# Sequencer.net
KiCad netlist of a schematic drawn in EAGLE
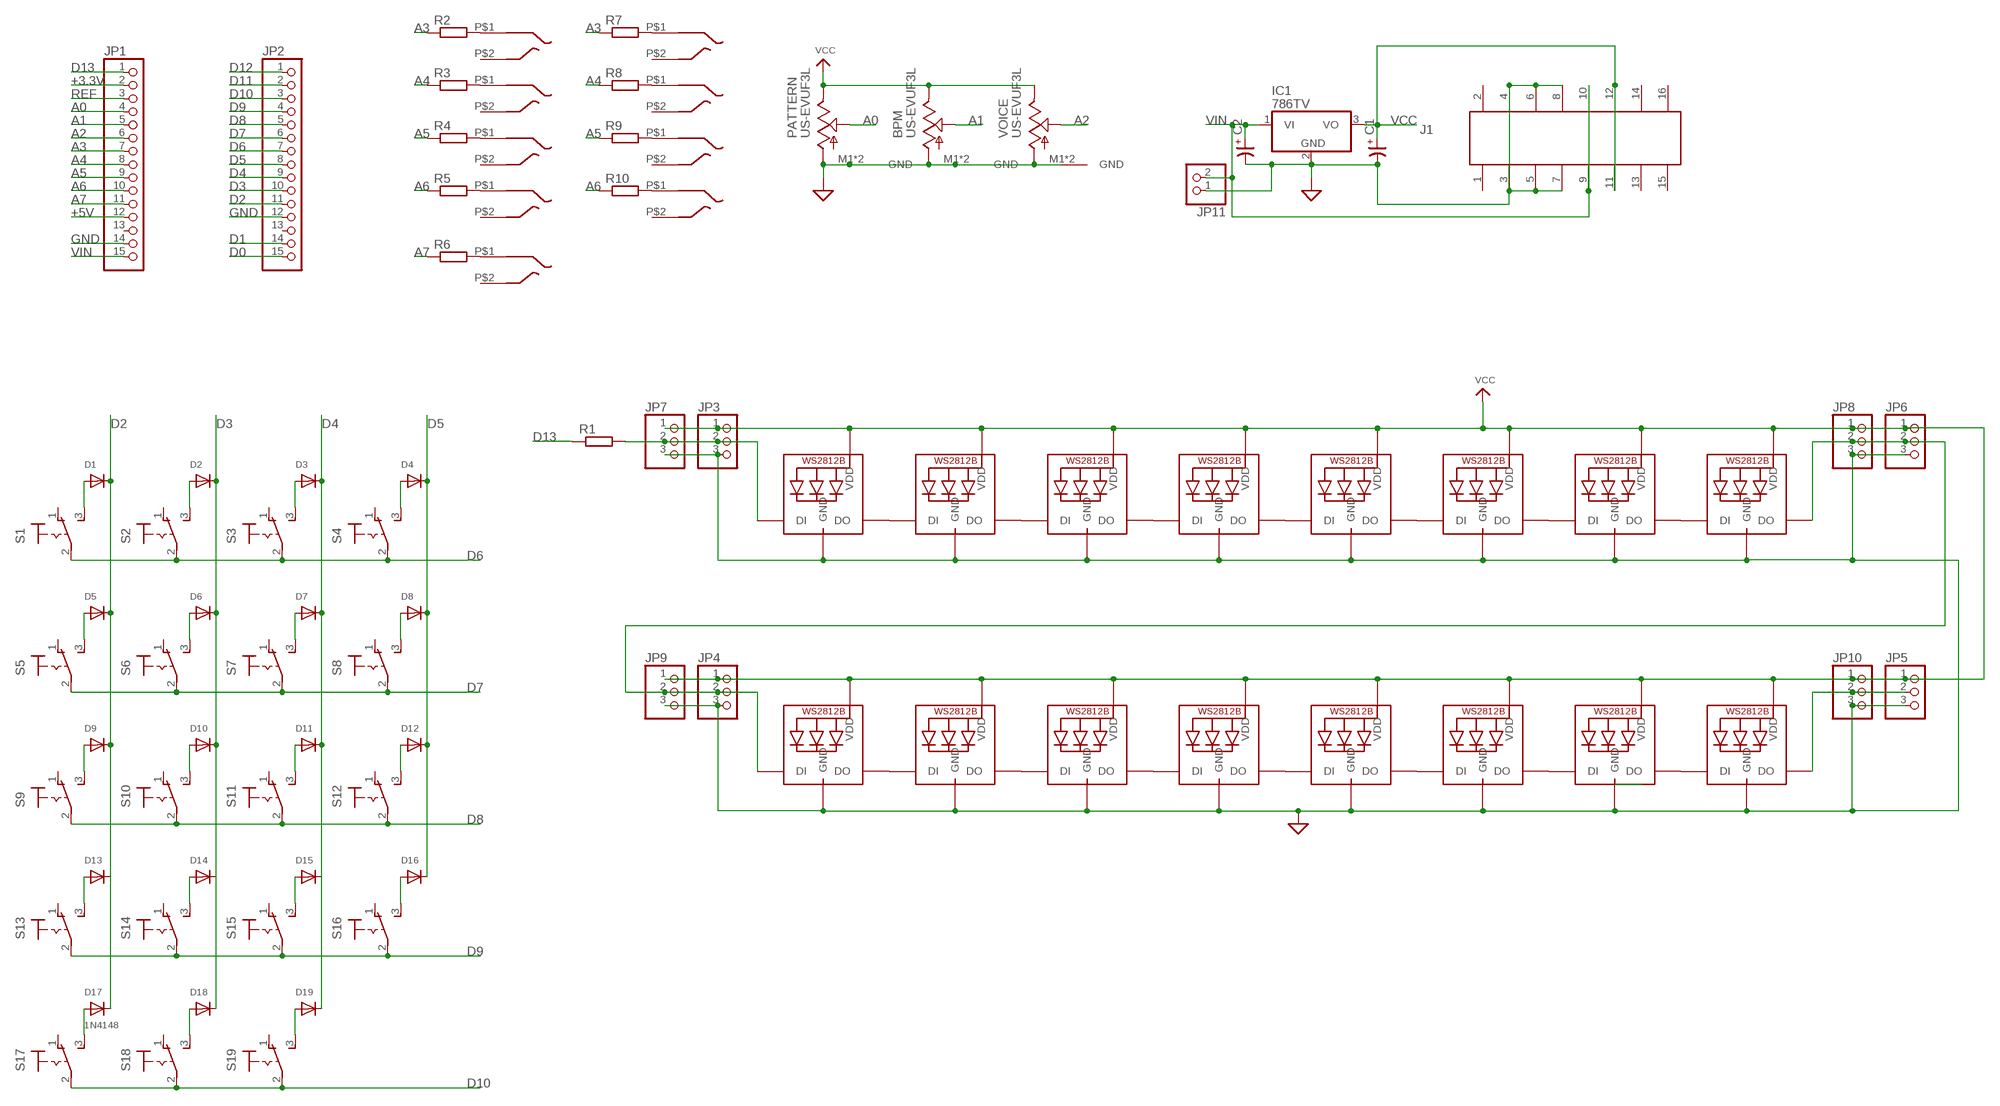
[diagram p0: schematic, sheet 1]

(export (version "E")
  (design (tool "Eeschema 10.0.6"))
  (components
    (comp (ref "BPM")
      (value "US-EVUF3L")
      (footprint "eagle-import:7.5MM")
      (libsource (lib "eagle-import") (part "US-EVULF3"))
    )
    (comp (ref "C1")
      (value "CP-E-025X065")
      (footprint "eagle-import:E-025X065")
      (libsource (lib "eagle-import") (part "CP-E-025X065"))
    )
    (comp (ref "C2")
      (value "CP-E-025X065")
      (footprint "eagle-import:E-025X065")
      (libsource (lib "eagle-import") (part "CP-E-025X065"))
    )
    (comp (ref "D1")
      (value "DIODEDO-1N4148")
      (footprint "eagle-import:DO-1N4148")
      (libsource (lib "eagle-import") (part "DIODEDO-1N4148"))
    )
    (comp (ref "D2")
      (value "DIODEDO-1N4148")
      (footprint "eagle-import:DO-1N4148")
      (libsource (lib "eagle-import") (part "DIODEDO-1N4148"))
    )
    (comp (ref "D3")
      (value "DIODEDO-1N4148")
      (footprint "eagle-import:DO-1N4148")
      (libsource (lib "eagle-import") (part "DIODEDO-1N4148"))
    )
    (comp (ref "D4")
      (value "DIODEDO-1N4148")
      (footprint "eagle-import:DO-1N4148")
      (libsource (lib "eagle-import") (part "DIODEDO-1N4148"))
    )
    (comp (ref "D5")
      (value "DIODEDO-1N4148")
      (footprint "eagle-import:DO-1N4148")
      (libsource (lib "eagle-import") (part "DIODEDO-1N4148"))
    )
    (comp (ref "D6")
      (value "DIODEDO-1N4148")
      (footprint "eagle-import:DO-1N4148")
      (libsource (lib "eagle-import") (part "DIODEDO-1N4148"))
    )
    (comp (ref "D7")
      (value "DIODEDO-1N4148")
      (footprint "eagle-import:DO-1N4148")
      (libsource (lib "eagle-import") (part "DIODEDO-1N4148"))
    )
    (comp (ref "D8")
      (value "DIODEDO-1N4148")
      (footprint "eagle-import:DO-1N4148")
      (libsource (lib "eagle-import") (part "DIODEDO-1N4148"))
    )
    (comp (ref "D9")
      (value "DIODEDO-1N4148")
      (footprint "eagle-import:DO-1N4148")
      (libsource (lib "eagle-import") (part "DIODEDO-1N4148"))
    )
    (comp (ref "D10")
      (value "DIODEDO-1N4148")
      (footprint "eagle-import:DO-1N4148")
      (libsource (lib "eagle-import") (part "DIODEDO-1N4148"))
    )
    (comp (ref "D11")
      (value "DIODEDO-1N4148")
      (footprint "eagle-import:DO-1N4148")
      (libsource (lib "eagle-import") (part "DIODEDO-1N4148"))
    )
    (comp (ref "D12")
      (value "DIODEDO-1N4148")
      (footprint "eagle-import:DO-1N4148")
      (libsource (lib "eagle-import") (part "DIODEDO-1N4148"))
    )
    (comp (ref "D13")
      (value "DIODEDO-1N4148")
      (footprint "eagle-import:DO-1N4148")
      (libsource (lib "eagle-import") (part "DIODEDO-1N4148"))
    )
    (comp (ref "D14")
      (value "DIODEDO-1N4148")
      (footprint "eagle-import:DO-1N4148")
      (libsource (lib "eagle-import") (part "DIODEDO-1N4148"))
    )
    (comp (ref "D15")
      (value "DIODEDO-1N4148")
      (footprint "eagle-import:DO-1N4148")
      (libsource (lib "eagle-import") (part "DIODEDO-1N4148"))
    )
    (comp (ref "D16")
      (value "DIODEDO-1N4148")
      (footprint "eagle-import:DO-1N4148")
      (libsource (lib "eagle-import") (part "DIODEDO-1N4148"))
    )
    (comp (ref "D17")
      (value "1N4148")
      (footprint "eagle-import:DO-1N4148")
      (libsource (lib "eagle-import") (part "DIODEDO-1N4148"))
    )
    (comp (ref "D18")
      (value "DIODEDO-1N4148")
      (footprint "eagle-import:DO-1N4148")
      (libsource (lib "eagle-import") (part "DIODEDO-1N4148"))
    )
    (comp (ref "D19")
      (value "DIODEDO-1N4148")
      (footprint "eagle-import:DO-1N4148")
      (libsource (lib "eagle-import") (part "DIODEDO-1N4148"))
    )
    (comp (ref "IC1")
      (value "786TV")
      (footprint "eagle-import:TO220V")
      (libsource (lib "eagle-import") (part "78TV6"))
    )
    (comp (ref "J1")
      (value "61201622323")
      (footprint "eagle-import:61201622323")
      (libsource (lib "eagle-import") (part "61201622323"))
    )
    (comp (ref "JP1")
      (value "PINHD-1X15")
      (footprint "eagle-import:1X15")
      (libsource (lib "eagle-import") (part "PINHD-1X15"))
    )
    (comp (ref "JP2")
      (value "PINHD-1X15")
      (footprint "eagle-import:1X15")
      (libsource (lib "eagle-import") (part "PINHD-1X15"))
    )
    (comp (ref "JP3")
      (value "PINHD-1X3CB")
      (footprint "eagle-import:1X03-CLEANBIG")
      (libsource (lib "eagle-import") (part "PINHD-1X3CB"))
    )
    (comp (ref "JP4")
      (value "PINHD-1X3CB")
      (footprint "eagle-import:1X03-CLEANBIG")
      (libsource (lib "eagle-import") (part "PINHD-1X3CB"))
    )
    (comp (ref "JP5")
      (value "PINHD-1X3CB")
      (footprint "eagle-import:1X03-CLEANBIG")
      (libsource (lib "eagle-import") (part "PINHD-1X3CB"))
    )
    (comp (ref "JP6")
      (value "PINHD-1X3CB")
      (footprint "eagle-import:1X03-CLEANBIG")
      (libsource (lib "eagle-import") (part "PINHD-1X3CB"))
    )
    (comp (ref "JP7")
      (value "PINHD-1X3CB")
      (footprint "eagle-import:1X03-CLEANBIG")
      (libsource (lib "eagle-import") (part "PINHD-1X3CB"))
    )
    (comp (ref "JP8")
      (value "PINHD-1X3CB")
      (footprint "eagle-import:1X03-CLEANBIG")
      (libsource (lib "eagle-import") (part "PINHD-1X3CB"))
    )
    (comp (ref "JP9")
      (value "PINHD-1X3CB")
      (footprint "eagle-import:1X03-CLEANBIG")
      (libsource (lib "eagle-import") (part "PINHD-1X3CB"))
    )
    (comp (ref "JP10")
      (value "PINHD-1X3CB")
      (footprint "eagle-import:1X03-CLEANBIG")
      (libsource (lib "eagle-import") (part "PINHD-1X3CB"))
    )
    (comp (ref "JP11")
      (value "PINHD-1X2")
      (footprint "eagle-import:1X02")
      (libsource (lib "eagle-import") (part "PINHD-1X2"))
    )
    (comp (ref "LED1")
      (value "WS2812B5050")
      (footprint "eagle-import:WS2812B")
      (libsource (lib "eagle-import") (part "WS2812B5050"))
    )
    (comp (ref "LED2")
      (value "WS2812B5050")
      (footprint "eagle-import:WS2812B")
      (libsource (lib "eagle-import") (part "WS2812B5050"))
    )
    (comp (ref "LED3")
      (value "WS2812B5050")
      (footprint "eagle-import:WS2812B")
      (libsource (lib "eagle-import") (part "WS2812B5050"))
    )
    (comp (ref "LED4")
      (value "WS2812B5050")
      (footprint "eagle-import:WS2812B")
      (libsource (lib "eagle-import") (part "WS2812B5050"))
    )
    (comp (ref "LED5")
      (value "WS2812B5050")
      (footprint "eagle-import:WS2812B")
      (libsource (lib "eagle-import") (part "WS2812B5050"))
    )
    (comp (ref "LED6")
      (value "WS2812B5050")
      (footprint "eagle-import:WS2812B")
      (libsource (lib "eagle-import") (part "WS2812B5050"))
    )
    (comp (ref "LED7")
      (value "WS2812B5050")
      (footprint "eagle-import:WS2812B")
      (libsource (lib "eagle-import") (part "WS2812B5050"))
    )
    (comp (ref "LED8")
      (value "WS2812B5050")
      (footprint "eagle-import:WS2812B")
      (libsource (lib "eagle-import") (part "WS2812B5050"))
    )
    (comp (ref "LED9")
      (value "WS2812B5050")
      (footprint "eagle-import:WS2812B")
      (libsource (lib "eagle-import") (part "WS2812B5050"))
    )
    (comp (ref "LED10")
      (value "WS2812B5050")
      (footprint "eagle-import:WS2812B")
      (libsource (lib "eagle-import") (part "WS2812B5050"))
    )
    (comp (ref "LED11")
      (value "WS2812B5050")
      (footprint "eagle-import:WS2812B")
      (libsource (lib "eagle-import") (part "WS2812B5050"))
    )
    (comp (ref "LED12")
      (value "WS2812B5050")
      (footprint "eagle-import:WS2812B")
      (libsource (lib "eagle-import") (part "WS2812B5050"))
    )
    (comp (ref "LED13")
      (value "WS2812B5050")
      (footprint "eagle-import:WS2812B")
      (libsource (lib "eagle-import") (part "WS2812B5050"))
    )
    (comp (ref "LED14")
      (value "WS2812B5050")
      (footprint "eagle-import:WS2812B")
      (libsource (lib "eagle-import") (part "WS2812B5050"))
    )
    (comp (ref "LED15")
      (value "WS2812B5050")
      (footprint "eagle-import:WS2812B")
      (libsource (lib "eagle-import") (part "WS2812B5050"))
    )
    (comp (ref "LED16")
      (value "WS2812B5050")
      (footprint "eagle-import:WS2812B")
      (libsource (lib "eagle-import") (part "WS2812B5050"))
    )
    (comp (ref "PATTERN")
      (value "US-EVUF3L")
      (footprint "eagle-import:7.5MM")
      (libsource (lib "eagle-import") (part "US-EVULF3"))
    )
    (comp (ref "R1")
      (value "R-EU_0207/10")
      (footprint "eagle-import:0207_10")
      (libsource (lib "eagle-import") (part "R-EU_0207/10"))
    )
    (comp (ref "R2")
      (value "R-EU_0207/10")
      (footprint "eagle-import:0207_10")
      (libsource (lib "eagle-import") (part "R-EU_0207/10"))
    )
    (comp (ref "R3")
      (value "R-EU_0207/10")
      (footprint "eagle-import:0207_10")
      (libsource (lib "eagle-import") (part "R-EU_0207/10"))
    )
    (comp (ref "R4")
      (value "R-EU_0207/10")
      (footprint "eagle-import:0207_10")
      (libsource (lib "eagle-import") (part "R-EU_0207/10"))
    )
    (comp (ref "R5")
      (value "R-EU_0207/10")
      (footprint "eagle-import:0207_10")
      (libsource (lib "eagle-import") (part "R-EU_0207/10"))
    )
    (comp (ref "R6")
      (value "R-EU_0207/10")
      (footprint "eagle-import:0207_10")
      (libsource (lib "eagle-import") (part "R-EU_0207/10"))
    )
    (comp (ref "R7")
      (value "R-EU_0207/10")
      (footprint "eagle-import:0207_10")
      (libsource (lib "eagle-import") (part "R-EU_0207/10"))
    )
    (comp (ref "R8")
      (value "R-EU_0207/10")
      (footprint "eagle-import:0207_10")
      (libsource (lib "eagle-import") (part "R-EU_0207/10"))
    )
    (comp (ref "R9")
      (value "R-EU_0207/10")
      (footprint "eagle-import:0207_10")
      (libsource (lib "eagle-import") (part "R-EU_0207/10"))
    )
    (comp (ref "R10")
      (value "R-EU_0207/10")
      (footprint "eagle-import:0207_10")
      (libsource (lib "eagle-import") (part "R-EU_0207/10"))
    )
    (comp (ref "S1")
      (value "CHINESIUM-TOGGLE-SWITCH")
      (footprint "eagle-import:CHINESIUM-TOGGLE-SWITCH")
      (libsource (lib "eagle-import") (part "CHINESIUM-TOGGLE-SWITCH"))
    )
    (comp (ref "S2")
      (value "CHINESIUM-TOGGLE-SWITCH")
      (footprint "eagle-import:CHINESIUM-TOGGLE-SWITCH")
      (libsource (lib "eagle-import") (part "CHINESIUM-TOGGLE-SWITCH"))
    )
    (comp (ref "S3")
      (value "CHINESIUM-TOGGLE-SWITCH")
      (footprint "eagle-import:CHINESIUM-TOGGLE-SWITCH")
      (libsource (lib "eagle-import") (part "CHINESIUM-TOGGLE-SWITCH"))
    )
    (comp (ref "S4")
      (value "CHINESIUM-TOGGLE-SWITCH")
      (footprint "eagle-import:CHINESIUM-TOGGLE-SWITCH")
      (libsource (lib "eagle-import") (part "CHINESIUM-TOGGLE-SWITCH"))
    )
    (comp (ref "S5")
      (value "CHINESIUM-TOGGLE-SWITCH")
      (footprint "eagle-import:CHINESIUM-TOGGLE-SWITCH")
      (libsource (lib "eagle-import") (part "CHINESIUM-TOGGLE-SWITCH"))
    )
    (comp (ref "S6")
      (value "CHINESIUM-TOGGLE-SWITCH")
      (footprint "eagle-import:CHINESIUM-TOGGLE-SWITCH")
      (libsource (lib "eagle-import") (part "CHINESIUM-TOGGLE-SWITCH"))
    )
    (comp (ref "S7")
      (value "CHINESIUM-TOGGLE-SWITCH")
      (footprint "eagle-import:CHINESIUM-TOGGLE-SWITCH")
      (libsource (lib "eagle-import") (part "CHINESIUM-TOGGLE-SWITCH"))
    )
    (comp (ref "S8")
      (value "CHINESIUM-TOGGLE-SWITCH")
      (footprint "eagle-import:CHINESIUM-TOGGLE-SWITCH")
      (libsource (lib "eagle-import") (part "CHINESIUM-TOGGLE-SWITCH"))
    )
    (comp (ref "S9")
      (value "CHINESIUM-TOGGLE-SWITCH")
      (footprint "eagle-import:CHINESIUM-TOGGLE-SWITCH")
      (libsource (lib "eagle-import") (part "CHINESIUM-TOGGLE-SWITCH"))
    )
    (comp (ref "S10")
      (value "CHINESIUM-TOGGLE-SWITCH")
      (footprint "eagle-import:CHINESIUM-TOGGLE-SWITCH")
      (libsource (lib "eagle-import") (part "CHINESIUM-TOGGLE-SWITCH"))
    )
    (comp (ref "S11")
      (value "CHINESIUM-TOGGLE-SWITCH")
      (footprint "eagle-import:CHINESIUM-TOGGLE-SWITCH")
      (libsource (lib "eagle-import") (part "CHINESIUM-TOGGLE-SWITCH"))
    )
    (comp (ref "S12")
      (value "CHINESIUM-TOGGLE-SWITCH")
      (footprint "eagle-import:CHINESIUM-TOGGLE-SWITCH")
      (libsource (lib "eagle-import") (part "CHINESIUM-TOGGLE-SWITCH"))
    )
    (comp (ref "S13")
      (value "CHINESIUM-TOGGLE-SWITCH")
      (footprint "eagle-import:CHINESIUM-TOGGLE-SWITCH")
      (libsource (lib "eagle-import") (part "CHINESIUM-TOGGLE-SWITCH"))
    )
    (comp (ref "S14")
      (value "CHINESIUM-TOGGLE-SWITCH")
      (footprint "eagle-import:CHINESIUM-TOGGLE-SWITCH")
      (libsource (lib "eagle-import") (part "CHINESIUM-TOGGLE-SWITCH"))
    )
    (comp (ref "S15")
      (value "CHINESIUM-TOGGLE-SWITCH")
      (footprint "eagle-import:CHINESIUM-TOGGLE-SWITCH")
      (libsource (lib "eagle-import") (part "CHINESIUM-TOGGLE-SWITCH"))
    )
    (comp (ref "S16")
      (value "CHINESIUM-TOGGLE-SWITCH")
      (footprint "eagle-import:CHINESIUM-TOGGLE-SWITCH")
      (libsource (lib "eagle-import") (part "CHINESIUM-TOGGLE-SWITCH"))
    )
    (comp (ref "S17")
      (value "CHINESIUM-TOGGLE-SWITCH")
      (footprint "eagle-import:CHINESIUM-TOGGLE-SWITCH")
      (libsource (lib "eagle-import") (part "CHINESIUM-TOGGLE-SWITCH"))
    )
    (comp (ref "S18")
      (value "CHINESIUM-TOGGLE-SWITCH")
      (footprint "eagle-import:CHINESIUM-TOGGLE-SWITCH")
      (libsource (lib "eagle-import") (part "CHINESIUM-TOGGLE-SWITCH"))
    )
    (comp (ref "S19")
      (value "CHINESIUM-TOGGLE-SWITCH")
      (footprint "eagle-import:CHINESIUM-TOGGLE-SWITCH")
      (libsource (lib "eagle-import") (part "CHINESIUM-TOGGLE-SWITCH"))
    )
    (comp (ref "U$1")
      (value "3.5MM-AUDIO")
      (footprint "eagle-import:3.5MM-AUDIO")
      (libsource (lib "eagle-import") (part "3.5MM-AUDIO"))
    )
    (comp (ref "U$2")
      (value "3.5MM-AUDIO")
      (footprint "eagle-import:3.5MM-AUDIO")
      (libsource (lib "eagle-import") (part "3.5MM-AUDIO"))
    )
    (comp (ref "U$3")
      (value "3.5MM-AUDIO")
      (footprint "eagle-import:3.5MM-AUDIO")
      (libsource (lib "eagle-import") (part "3.5MM-AUDIO"))
    )
    (comp (ref "U$4")
      (value "3.5MM-AUDIO")
      (footprint "eagle-import:3.5MM-AUDIO")
      (libsource (lib "eagle-import") (part "3.5MM-AUDIO"))
    )
    (comp (ref "U$5")
      (value "3.5MM-AUDIO")
      (footprint "eagle-import:3.5MM-AUDIO")
      (libsource (lib "eagle-import") (part "3.5MM-AUDIO"))
    )
    (comp (ref "U$6")
      (value "3.5MM-AUDIO")
      (footprint "eagle-import:3.5MM-AUDIO")
      (libsource (lib "eagle-import") (part "3.5MM-AUDIO"))
    )
    (comp (ref "U$7")
      (value "3.5MM-AUDIO")
      (footprint "eagle-import:3.5MM-AUDIO")
      (libsource (lib "eagle-import") (part "3.5MM-AUDIO"))
    )
    (comp (ref "U$8")
      (value "3.5MM-AUDIO")
      (footprint "eagle-import:3.5MM-AUDIO")
      (libsource (lib "eagle-import") (part "3.5MM-AUDIO"))
    )
    (comp (ref "U$9")
      (value "3.5MM-AUDIO")
      (footprint "eagle-import:3.5MM-AUDIO")
      (libsource (lib "eagle-import") (part "3.5MM-AUDIO"))
    )
    (comp (ref "VOICE")
      (value "US-EVUF3L")
      (footprint "eagle-import:7.5MM")
      (libsource (lib "eagle-import") (part "US-EVULF3"))
    )
  )
  (nets
    (net (code "1") (name "/+3.3V") (class "Default")
      (node (ref "JP1") (pin "2") (pinfunction "2_2") (pintype "passive"))
    )
    (net (code "2") (name "/+5V") (class "Default")
      (node (ref "JP1") (pin "12") (pinfunction "12_12") (pintype "passive"))
    )
    (net (code "3") (name "/A0") (class "Default")
      (node (ref "JP1") (pin "4") (pinfunction "4_4") (pintype "passive"))
      (node (ref "PATTERN") (pin "2") (pinfunction "S_2") (pintype "passive"))
    )
    (net (code "4") (name "/A1") (class "Default")
      (node (ref "BPM") (pin "2") (pinfunction "S_2") (pintype "passive"))
      (node (ref "JP1") (pin "5") (pinfunction "5_5") (pintype "passive"))
    )
    (net (code "5") (name "/A2") (class "Default")
      (node (ref "JP1") (pin "6") (pinfunction "6_6") (pintype "passive"))
      (node (ref "VOICE") (pin "2") (pinfunction "S_2") (pintype "passive"))
    )
    (net (code "6") (name "/A3") (class "Default")
      (node (ref "JP1") (pin "7") (pinfunction "7_7") (pintype "passive"))
      (node (ref "R2") (pin "1") (pinfunction "1_1") (pintype "passive"))
      (node (ref "R7") (pin "1") (pinfunction "1_1") (pintype "passive"))
    )
    (net (code "7") (name "/A4") (class "Default")
      (node (ref "JP1") (pin "8") (pinfunction "8_8") (pintype "passive"))
      (node (ref "R3") (pin "1") (pinfunction "1_1") (pintype "passive"))
      (node (ref "R8") (pin "1") (pinfunction "1_1") (pintype "passive"))
    )
    (net (code "8") (name "/A5") (class "Default")
      (node (ref "JP1") (pin "9") (pinfunction "9_9") (pintype "passive"))
      (node (ref "R4") (pin "1") (pinfunction "1_1") (pintype "passive"))
      (node (ref "R9") (pin "1") (pinfunction "1_1") (pintype "passive"))
    )
    (net (code "9") (name "/A6") (class "Default")
      (node (ref "JP1") (pin "10") (pinfunction "10_10") (pintype "passive"))
      (node (ref "R10") (pin "1") (pinfunction "1_1") (pintype "passive"))
      (node (ref "R5") (pin "1") (pinfunction "1_1") (pintype "passive"))
    )
    (net (code "10") (name "/A7") (class "Default")
      (node (ref "JP1") (pin "11") (pinfunction "11_11") (pintype "passive"))
      (node (ref "R6") (pin "1") (pinfunction "1_1") (pintype "passive"))
    )
    (net (code "11") (name "/D0") (class "Default")
      (node (ref "JP2") (pin "15") (pinfunction "15_15") (pintype "passive"))
    )
    (net (code "12") (name "/D1") (class "Default")
      (node (ref "JP2") (pin "14") (pinfunction "14_14") (pintype "passive"))
    )
    (net (code "13") (name "/D2") (class "Default")
      (node (ref "D1") (pin "C") (pinfunction "C_C") (pintype "passive"))
      (node (ref "D13") (pin "C") (pinfunction "C_C") (pintype "passive"))
      (node (ref "D17") (pin "C") (pinfunction "C_C") (pintype "passive"))
      (node (ref "D5") (pin "C") (pinfunction "C_C") (pintype "passive"))
      (node (ref "D9") (pin "C") (pinfunction "C_C") (pintype "passive"))
      (node (ref "JP2") (pin "11") (pinfunction "11_11") (pintype "passive"))
    )
    (net (code "14") (name "/D3") (class "Default")
      (node (ref "D10") (pin "C") (pinfunction "C_C") (pintype "passive"))
      (node (ref "D14") (pin "C") (pinfunction "C_C") (pintype "passive"))
      (node (ref "D18") (pin "C") (pinfunction "C_C") (pintype "passive"))
      (node (ref "D2") (pin "C") (pinfunction "C_C") (pintype "passive"))
      (node (ref "D6") (pin "C") (pinfunction "C_C") (pintype "passive"))
      (node (ref "JP2") (pin "10") (pinfunction "10_10") (pintype "passive"))
    )
    (net (code "15") (name "/D4") (class "Default")
      (node (ref "D11") (pin "C") (pinfunction "C_C") (pintype "passive"))
      (node (ref "D15") (pin "C") (pinfunction "C_C") (pintype "passive"))
      (node (ref "D19") (pin "C") (pinfunction "C_C") (pintype "passive"))
      (node (ref "D3") (pin "C") (pinfunction "C_C") (pintype "passive"))
      (node (ref "D7") (pin "C") (pinfunction "C_C") (pintype "passive"))
      (node (ref "JP2") (pin "9") (pinfunction "9_9") (pintype "passive"))
    )
    (net (code "16") (name "/D5") (class "Default")
      (node (ref "D12") (pin "C") (pinfunction "C_C") (pintype "passive"))
      (node (ref "D16") (pin "C") (pinfunction "C_C") (pintype "passive"))
      (node (ref "D4") (pin "C") (pinfunction "C_C") (pintype "passive"))
      (node (ref "D8") (pin "C") (pinfunction "C_C") (pintype "passive"))
      (node (ref "JP2") (pin "8") (pinfunction "8_8") (pintype "passive"))
    )
    (net (code "17") (name "/D6") (class "Default")
      (node (ref "JP2") (pin "7") (pinfunction "7_7") (pintype "passive"))
      (node (ref "S1") (pin "2") (pinfunction "P_2") (pintype "passive"))
      (node (ref "S2") (pin "2") (pinfunction "P_2") (pintype "passive"))
      (node (ref "S3") (pin "2") (pinfunction "P_2") (pintype "passive"))
      (node (ref "S4") (pin "2") (pinfunction "P_2") (pintype "passive"))
    )
    (net (code "18") (name "/D7") (class "Default")
      (node (ref "JP2") (pin "6") (pinfunction "6_6") (pintype "passive"))
      (node (ref "S5") (pin "2") (pinfunction "P_2") (pintype "passive"))
      (node (ref "S6") (pin "2") (pinfunction "P_2") (pintype "passive"))
      (node (ref "S7") (pin "2") (pinfunction "P_2") (pintype "passive"))
      (node (ref "S8") (pin "2") (pinfunction "P_2") (pintype "passive"))
    )
    (net (code "19") (name "/D8") (class "Default")
      (node (ref "JP2") (pin "5") (pinfunction "5_5") (pintype "passive"))
      (node (ref "S10") (pin "2") (pinfunction "P_2") (pintype "passive"))
      (node (ref "S11") (pin "2") (pinfunction "P_2") (pintype "passive"))
      (node (ref "S12") (pin "2") (pinfunction "P_2") (pintype "passive"))
      (node (ref "S9") (pin "2") (pinfunction "P_2") (pintype "passive"))
    )
    (net (code "20") (name "/D9") (class "Default")
      (node (ref "JP2") (pin "4") (pinfunction "4_4") (pintype "passive"))
      (node (ref "S13") (pin "2") (pinfunction "P_2") (pintype "passive"))
      (node (ref "S14") (pin "2") (pinfunction "P_2") (pintype "passive"))
      (node (ref "S15") (pin "2") (pinfunction "P_2") (pintype "passive"))
      (node (ref "S16") (pin "2") (pinfunction "P_2") (pintype "passive"))
    )
    (net (code "21") (name "/D10") (class "Default")
      (node (ref "JP2") (pin "3") (pinfunction "3_3") (pintype "passive"))
      (node (ref "S17") (pin "2") (pinfunction "P_2") (pintype "passive"))
      (node (ref "S18") (pin "2") (pinfunction "P_2") (pintype "passive"))
      (node (ref "S19") (pin "2") (pinfunction "P_2") (pintype "passive"))
    )
    (net (code "22") (name "/D11") (class "Default")
      (node (ref "JP2") (pin "2") (pinfunction "2_2") (pintype "passive"))
    )
    (net (code "23") (name "/D12") (class "Default")
      (node (ref "JP2") (pin "1") (pinfunction "1_1") (pintype "passive"))
    )
    (net (code "24") (name "/D13") (class "Default")
      (node (ref "JP1") (pin "1") (pinfunction "1_1") (pintype "passive"))
      (node (ref "R1") (pin "1") (pinfunction "1_1") (pintype "passive"))
    )
    (net (code "25") (name "/REF") (class "Default")
      (node (ref "JP1") (pin "3") (pinfunction "3_3") (pintype "passive"))
    )
    (net (code "26") (name "/VIN") (class "Default")
      (node (ref "C2") (pin "+") (pinfunction "+_+") (pintype "passive"))
      (node (ref "IC1") (pin "1") (pinfunction "VI_1") (pintype "input"))
      (node (ref "J1") (pin "10") (pinfunction "10_10") (pintype "passive"))
      (node (ref "J1") (pin "9") (pinfunction "9_9") (pintype "passive"))
      (node (ref "JP1") (pin "15") (pinfunction "15_15") (pintype "passive"))
      (node (ref "JP11") (pin "2") (pinfunction "2_2") (pintype "passive"))
    )
    (net (code "27") (name "Net-(LED1-DI)") (class "Default")
      (node (ref "JP3") (pin "2") (pinfunction "2_2") (pintype "passive"))
      (node (ref "JP7") (pin "2") (pinfunction "2_2") (pintype "passive"))
      (node (ref "LED1") (pin "4-DIN") (pinfunction "DI_4-DIN") (pintype "input"))
      (node (ref "R1") (pin "2") (pinfunction "2_2") (pintype "passive"))
    )
    (net (code "28") (name "Net-(LED1-DO)") (class "Default")
      (node (ref "LED1") (pin "2-DOUT") (pinfunction "DO_2-DOUT") (pintype "output"))
      (node (ref "LED2") (pin "4-DIN") (pinfunction "DI_4-DIN") (pintype "input"))
    )
    (net (code "29") (name "Net-(LED2-DO)") (class "Default")
      (node (ref "LED2") (pin "2-DOUT") (pinfunction "DO_2-DOUT") (pintype "output"))
      (node (ref "LED3") (pin "4-DIN") (pinfunction "DI_4-DIN") (pintype "input"))
    )
    (net (code "30") (name "Net-(LED3-DO)") (class "Default")
      (node (ref "LED3") (pin "2-DOUT") (pinfunction "DO_2-DOUT") (pintype "output"))
      (node (ref "LED4") (pin "4-DIN") (pinfunction "DI_4-DIN") (pintype "input"))
    )
    (net (code "31") (name "Net-(LED4-DO)") (class "Default")
      (node (ref "LED4") (pin "2-DOUT") (pinfunction "DO_2-DOUT") (pintype "output"))
      (node (ref "LED5") (pin "4-DIN") (pinfunction "DI_4-DIN") (pintype "input"))
    )
    (net (code "32") (name "Net-(LED5-DO)") (class "Default")
      (node (ref "LED5") (pin "2-DOUT") (pinfunction "DO_2-DOUT") (pintype "output"))
      (node (ref "LED6") (pin "4-DIN") (pinfunction "DI_4-DIN") (pintype "input"))
    )
    (net (code "33") (name "Net-(LED6-DO)") (class "Default")
      (node (ref "LED6") (pin "2-DOUT") (pinfunction "DO_2-DOUT") (pintype "output"))
      (node (ref "LED7") (pin "4-DIN") (pinfunction "DI_4-DIN") (pintype "input"))
    )
    (net (code "34") (name "Net-(LED7-DO)") (class "Default")
      (node (ref "LED7") (pin "2-DOUT") (pinfunction "DO_2-DOUT") (pintype "output"))
      (node (ref "LED8") (pin "4-DIN") (pinfunction "DI_4-DIN") (pintype "input"))
    )
    (net (code "35") (name "Net-(LED8-DO)") (class "Default")
      (node (ref "JP4") (pin "2") (pinfunction "2_2") (pintype "passive"))
      (node (ref "JP6") (pin "2") (pinfunction "2_2") (pintype "passive"))
      (node (ref "JP8") (pin "2") (pinfunction "2_2") (pintype "passive"))
      (node (ref "JP9") (pin "2") (pinfunction "2_2") (pintype "passive"))
      (node (ref "LED8") (pin "2-DOUT") (pinfunction "DO_2-DOUT") (pintype "output"))
      (node (ref "LED9") (pin "4-DIN") (pinfunction "DI_4-DIN") (pintype "input"))
    )
    (net (code "36") (name "Net-(LED10-DI)") (class "Default")
      (node (ref "LED10") (pin "4-DIN") (pinfunction "DI_4-DIN") (pintype "input"))
      (node (ref "LED9") (pin "2-DOUT") (pinfunction "DO_2-DOUT") (pintype "output"))
    )
    (net (code "37") (name "Net-(LED10-DO)") (class "Default")
      (node (ref "LED10") (pin "2-DOUT") (pinfunction "DO_2-DOUT") (pintype "output"))
      (node (ref "LED11") (pin "4-DIN") (pinfunction "DI_4-DIN") (pintype "input"))
    )
    (net (code "38") (name "Net-(LED11-DO)") (class "Default")
      (node (ref "LED11") (pin "2-DOUT") (pinfunction "DO_2-DOUT") (pintype "output"))
      (node (ref "LED12") (pin "4-DIN") (pinfunction "DI_4-DIN") (pintype "input"))
    )
    (net (code "39") (name "Net-(LED12-DO)") (class "Default")
      (node (ref "LED12") (pin "2-DOUT") (pinfunction "DO_2-DOUT") (pintype "output"))
      (node (ref "LED13") (pin "4-DIN") (pinfunction "DI_4-DIN") (pintype "input"))
    )
    (net (code "40") (name "Net-(LED13-DO)") (class "Default")
      (node (ref "LED13") (pin "2-DOUT") (pinfunction "DO_2-DOUT") (pintype "output"))
      (node (ref "LED14") (pin "4-DIN") (pinfunction "DI_4-DIN") (pintype "input"))
    )
    (net (code "41") (name "Net-(LED14-DO)") (class "Default")
      (node (ref "LED14") (pin "2-DOUT") (pinfunction "DO_2-DOUT") (pintype "output"))
      (node (ref "LED15") (pin "4-DIN") (pinfunction "DI_4-DIN") (pintype "input"))
    )
    (net (code "42") (name "Net-(LED15-DO)") (class "Default")
      (node (ref "LED15") (pin "2-DOUT") (pinfunction "DO_2-DOUT") (pintype "output"))
      (node (ref "LED16") (pin "4-DIN") (pinfunction "DI_4-DIN") (pintype "input"))
    )
    (net (code "43") (name "Net-(LED16-DO)") (class "Default")
      (node (ref "JP10") (pin "2") (pinfunction "2_2") (pintype "passive"))
      (node (ref "JP5") (pin "2") (pinfunction "2_2") (pintype "passive"))
      (node (ref "LED16") (pin "2-DOUT") (pinfunction "DO_2-DOUT") (pintype "output"))
    )
    (net (code "44") (name "Net-(S1-S)") (class "Default")
      (node (ref "D1") (pin "A") (pinfunction "A_A") (pintype "passive"))
      (node (ref "S1") (pin "3") (pinfunction "S_3") (pintype "passive"))
    )
    (net (code "45") (name "Net-(S2-S)") (class "Default")
      (node (ref "D2") (pin "A") (pinfunction "A_A") (pintype "passive"))
      (node (ref "S2") (pin "3") (pinfunction "S_3") (pintype "passive"))
    )
    (net (code "46") (name "Net-(S3-S)") (class "Default")
      (node (ref "D3") (pin "A") (pinfunction "A_A") (pintype "passive"))
      (node (ref "S3") (pin "3") (pinfunction "S_3") (pintype "passive"))
    )
    (net (code "47") (name "Net-(S4-S)") (class "Default")
      (node (ref "D4") (pin "A") (pinfunction "A_A") (pintype "passive"))
      (node (ref "S4") (pin "3") (pinfunction "S_3") (pintype "passive"))
    )
    (net (code "48") (name "Net-(S5-S)") (class "Default")
      (node (ref "D5") (pin "A") (pinfunction "A_A") (pintype "passive"))
      (node (ref "S5") (pin "3") (pinfunction "S_3") (pintype "passive"))
    )
    (net (code "49") (name "Net-(S6-S)") (class "Default")
      (node (ref "D6") (pin "A") (pinfunction "A_A") (pintype "passive"))
      (node (ref "S6") (pin "3") (pinfunction "S_3") (pintype "passive"))
    )
    (net (code "50") (name "Net-(S7-S)") (class "Default")
      (node (ref "D7") (pin "A") (pinfunction "A_A") (pintype "passive"))
      (node (ref "S7") (pin "3") (pinfunction "S_3") (pintype "passive"))
    )
    (net (code "51") (name "Net-(S8-S)") (class "Default")
      (node (ref "D8") (pin "A") (pinfunction "A_A") (pintype "passive"))
      (node (ref "S8") (pin "3") (pinfunction "S_3") (pintype "passive"))
    )
    (net (code "52") (name "Net-(S9-S)") (class "Default")
      (node (ref "D9") (pin "A") (pinfunction "A_A") (pintype "passive"))
      (node (ref "S9") (pin "3") (pinfunction "S_3") (pintype "passive"))
    )
    (net (code "53") (name "Net-(S10-S)") (class "Default")
      (node (ref "D10") (pin "A") (pinfunction "A_A") (pintype "passive"))
      (node (ref "S10") (pin "3") (pinfunction "S_3") (pintype "passive"))
    )
    (net (code "54") (name "Net-(S11-S)") (class "Default")
      (node (ref "D11") (pin "A") (pinfunction "A_A") (pintype "passive"))
      (node (ref "S11") (pin "3") (pinfunction "S_3") (pintype "passive"))
    )
    (net (code "55") (name "Net-(S12-S)") (class "Default")
      (node (ref "D12") (pin "A") (pinfunction "A_A") (pintype "passive"))
      (node (ref "S12") (pin "3") (pinfunction "S_3") (pintype "passive"))
    )
    (net (code "56") (name "Net-(S13-S)") (class "Default")
      (node (ref "D13") (pin "A") (pinfunction "A_A") (pintype "passive"))
      (node (ref "S13") (pin "3") (pinfunction "S_3") (pintype "passive"))
    )
    (net (code "57") (name "Net-(S14-S)") (class "Default")
      (node (ref "D14") (pin "A") (pinfunction "A_A") (pintype "passive"))
      (node (ref "S14") (pin "3") (pinfunction "S_3") (pintype "passive"))
    )
    (net (code "58") (name "Net-(S15-S)") (class "Default")
      (node (ref "D15") (pin "A") (pinfunction "A_A") (pintype "passive"))
      (node (ref "S15") (pin "3") (pinfunction "S_3") (pintype "passive"))
    )
    (net (code "59") (name "Net-(S16-S)") (class "Default")
      (node (ref "D16") (pin "A") (pinfunction "A_A") (pintype "passive"))
      (node (ref "S16") (pin "3") (pinfunction "S_3") (pintype "passive"))
    )
    (net (code "60") (name "Net-(S17-S)") (class "Default")
      (node (ref "D17") (pin "A") (pinfunction "A_A") (pintype "passive"))
      (node (ref "S17") (pin "3") (pinfunction "S_3") (pintype "passive"))
    )
    (net (code "61") (name "Net-(S18-S)") (class "Default")
      (node (ref "D18") (pin "A") (pinfunction "A_A") (pintype "passive"))
      (node (ref "S18") (pin "3") (pinfunction "S_3") (pintype "passive"))
    )
    (net (code "62") (name "Net-(S19-S)") (class "Default")
      (node (ref "D19") (pin "A") (pinfunction "A_A") (pintype "passive"))
      (node (ref "S19") (pin "3") (pinfunction "S_3") (pintype "passive"))
    )
    (net (code "63") (name "Net-(U$1-1)") (class "Default")
      (node (ref "R2") (pin "2") (pinfunction "2_2") (pintype "passive"))
      (node (ref "U$1") (pin "P$1") (pinfunction "1_P$1") (pintype "bidirectional"))
    )
    (net (code "64") (name "Net-(U$2-1)") (class "Default")
      (node (ref "R3") (pin "2") (pinfunction "2_2") (pintype "passive"))
      (node (ref "U$2") (pin "P$1") (pinfunction "1_P$1") (pintype "bidirectional"))
    )
    (net (code "65") (name "Net-(U$3-1)") (class "Default")
      (node (ref "R4") (pin "2") (pinfunction "2_2") (pintype "passive"))
      (node (ref "U$3") (pin "P$1") (pinfunction "1_P$1") (pintype "bidirectional"))
    )
    (net (code "66") (name "Net-(U$4-1)") (class "Default")
      (node (ref "R5") (pin "2") (pinfunction "2_2") (pintype "passive"))
      (node (ref "U$4") (pin "P$1") (pinfunction "1_P$1") (pintype "bidirectional"))
    )
    (net (code "67") (name "Net-(U$5-1)") (class "Default")
      (node (ref "R6") (pin "2") (pinfunction "2_2") (pintype "passive"))
      (node (ref "U$5") (pin "P$1") (pinfunction "1_P$1") (pintype "bidirectional"))
    )
    (net (code "68") (name "Net-(U$6-1)") (class "Default")
      (node (ref "R7") (pin "2") (pinfunction "2_2") (pintype "passive"))
      (node (ref "U$6") (pin "P$1") (pinfunction "1_P$1") (pintype "bidirectional"))
    )
    (net (code "69") (name "Net-(U$7-1)") (class "Default")
      (node (ref "R8") (pin "2") (pinfunction "2_2") (pintype "passive"))
      (node (ref "U$7") (pin "P$1") (pinfunction "1_P$1") (pintype "bidirectional"))
    )
    (net (code "70") (name "Net-(U$8-1)") (class "Default")
      (node (ref "R9") (pin "2") (pinfunction "2_2") (pintype "passive"))
      (node (ref "U$8") (pin "P$1") (pinfunction "1_P$1") (pintype "bidirectional"))
    )
    (net (code "71") (name "Net-(U$9-1)") (class "Default")
      (node (ref "R10") (pin "2") (pinfunction "2_2") (pintype "passive"))
      (node (ref "U$9") (pin "P$1") (pinfunction "1_P$1") (pintype "bidirectional"))
    )
    (net (code "72") (name "SUP") (class "Default")
      (node (ref "BPM") (pin "1") (pinfunction "A_1") (pintype "passive"))
      (node (ref "BPM") (pin "M1") (pinfunction "GND_M1") (pintype "bidirectional"))
      (node (ref "BPM") (pin "M2") (pinfunction "GND_M2") (pintype "bidirectional"))
      (node (ref "C1") (pin "-") (pinfunction "-_-") (pintype "passive"))
      (node (ref "C2") (pin "-") (pinfunction "-_-") (pintype "passive"))
      (node (ref "IC1") (pin "2") (pinfunction "GND_2") (pintype "passive"))
      (node (ref "J1") (pin "3") (pinfunction "3_3") (pintype "passive"))
      (node (ref "J1") (pin "4") (pinfunction "4_4") (pintype "passive"))
      (node (ref "J1") (pin "5") (pinfunction "5_5") (pintype "passive"))
      (node (ref "J1") (pin "6") (pinfunction "6_6") (pintype "passive"))
      (node (ref "J1") (pin "7") (pinfunction "7_7") (pintype "passive"))
      (node (ref "J1") (pin "8") (pinfunction "8_8") (pintype "passive"))
      (node (ref "JP1") (pin "14") (pinfunction "14_14") (pintype "passive"))
      (node (ref "JP10") (pin "3") (pinfunction "3_3") (pintype "passive"))
      (node (ref "JP11") (pin "1") (pinfunction "1_1") (pintype "passive"))
      (node (ref "JP2") (pin "12") (pinfunction "12_12") (pintype "passive"))
      (node (ref "JP3") (pin "3") (pinfunction "3_3") (pintype "passive"))
      (node (ref "JP4") (pin "3") (pinfunction "3_3") (pintype "passive"))
      (node (ref "JP5") (pin "3") (pinfunction "3_3") (pintype "passive"))
      (node (ref "JP6") (pin "3") (pinfunction "3_3") (pintype "passive"))
      (node (ref "JP7") (pin "3") (pinfunction "3_3") (pintype "passive"))
      (node (ref "JP8") (pin "3") (pinfunction "3_3") (pintype "passive"))
      (node (ref "JP9") (pin "3") (pinfunction "3_3") (pintype "passive"))
      (node (ref "LED1") (pin "3-GND") (pinfunction "GND_3-GND") (pintype "power_in"))
      (node (ref "LED10") (pin "3-GND") (pinfunction "GND_3-GND") (pintype "power_in"))
      (node (ref "LED11") (pin "3-GND") (pinfunction "GND_3-GND") (pintype "power_in"))
      (node (ref "LED12") (pin "3-GND") (pinfunction "GND_3-GND") (pintype "power_in"))
      (node (ref "LED13") (pin "3-GND") (pinfunction "GND_3-GND") (pintype "power_in"))
      (node (ref "LED14") (pin "3-GND") (pinfunction "GND_3-GND") (pintype "power_in"))
      (node (ref "LED15") (pin "3-GND") (pinfunction "GND_3-GND") (pintype "power_in"))
      (node (ref "LED16") (pin "3-GND") (pinfunction "GND_3-GND") (pintype "power_in"))
      (node (ref "LED2") (pin "3-GND") (pinfunction "GND_3-GND") (pintype "power_in"))
      (node (ref "LED3") (pin "3-GND") (pinfunction "GND_3-GND") (pintype "power_in"))
      (node (ref "LED4") (pin "3-GND") (pinfunction "GND_3-GND") (pintype "power_in"))
      (node (ref "LED5") (pin "3-GND") (pinfunction "GND_3-GND") (pintype "power_in"))
      (node (ref "LED6") (pin "3-GND") (pinfunction "GND_3-GND") (pintype "power_in"))
      (node (ref "LED7") (pin "3-GND") (pinfunction "GND_3-GND") (pintype "power_in"))
      (node (ref "LED8") (pin "3-GND") (pinfunction "GND_3-GND") (pintype "power_in"))
      (node (ref "LED9") (pin "3-GND") (pinfunction "GND_3-GND") (pintype "power_in"))
      (node (ref "PATTERN") (pin "1") (pinfunction "A_1") (pintype "passive"))
      (node (ref "PATTERN") (pin "M1") (pinfunction "GND_M1") (pintype "bidirectional"))
      (node (ref "PATTERN") (pin "M2") (pinfunction "GND_M2") (pintype "bidirectional"))
      (node (ref "VOICE") (pin "1") (pinfunction "A_1") (pintype "passive"))
      (node (ref "VOICE") (pin "M1") (pinfunction "GND_M1") (pintype "bidirectional"))
      (node (ref "VOICE") (pin "M2") (pinfunction "GND_M2") (pintype "bidirectional"))
    )
    (net (code "73") (name "VCC") (class "Default")
      (node (ref "BPM") (pin "3") (pinfunction "E_3") (pintype "passive"))
      (node (ref "C1") (pin "+") (pinfunction "+_+") (pintype "passive"))
      (node (ref "IC1") (pin "3") (pinfunction "VO_3") (pintype "passive"))
      (node (ref "J1") (pin "11") (pinfunction "11_11") (pintype "passive"))
      (node (ref "J1") (pin "12") (pinfunction "12_12") (pintype "passive"))
      (node (ref "JP10") (pin "1") (pinfunction "1_1") (pintype "passive"))
      (node (ref "JP3") (pin "1") (pinfunction "1_1") (pintype "passive"))
      (node (ref "JP4") (pin "1") (pinfunction "1_1") (pintype "passive"))
      (node (ref "JP5") (pin "1") (pinfunction "1_1") (pintype "passive"))
      (node (ref "JP6") (pin "1") (pinfunction "1_1") (pintype "passive"))
      (node (ref "JP7") (pin "1") (pinfunction "1_1") (pintype "passive"))
      (node (ref "JP8") (pin "1") (pinfunction "1_1") (pintype "passive"))
      (node (ref "JP9") (pin "1") (pinfunction "1_1") (pintype "passive"))
      (node (ref "LED1") (pin "1-VDD") (pinfunction "VDD_1-VDD") (pintype "power_in"))
      (node (ref "LED10") (pin "1-VDD") (pinfunction "VDD_1-VDD") (pintype "power_in"))
      (node (ref "LED11") (pin "1-VDD") (pinfunction "VDD_1-VDD") (pintype "power_in"))
      (node (ref "LED12") (pin "1-VDD") (pinfunction "VDD_1-VDD") (pintype "power_in"))
      (node (ref "LED13") (pin "1-VDD") (pinfunction "VDD_1-VDD") (pintype "power_in"))
      (node (ref "LED14") (pin "1-VDD") (pinfunction "VDD_1-VDD") (pintype "power_in"))
      (node (ref "LED15") (pin "1-VDD") (pinfunction "VDD_1-VDD") (pintype "power_in"))
      (node (ref "LED16") (pin "1-VDD") (pinfunction "VDD_1-VDD") (pintype "power_in"))
      (node (ref "LED2") (pin "1-VDD") (pinfunction "VDD_1-VDD") (pintype "power_in"))
      (node (ref "LED3") (pin "1-VDD") (pinfunction "VDD_1-VDD") (pintype "power_in"))
      (node (ref "LED4") (pin "1-VDD") (pinfunction "VDD_1-VDD") (pintype "power_in"))
      (node (ref "LED5") (pin "1-VDD") (pinfunction "VDD_1-VDD") (pintype "power_in"))
      (node (ref "LED6") (pin "1-VDD") (pinfunction "VDD_1-VDD") (pintype "power_in"))
      (node (ref "LED7") (pin "1-VDD") (pinfunction "VDD_1-VDD") (pintype "power_in"))
      (node (ref "LED8") (pin "1-VDD") (pinfunction "VDD_1-VDD") (pintype "power_in"))
      (node (ref "LED9") (pin "1-VDD") (pinfunction "VDD_1-VDD") (pintype "power_in"))
      (node (ref "PATTERN") (pin "3") (pinfunction "E_3") (pintype "passive"))
      (node (ref "VOICE") (pin "3") (pinfunction "E_3") (pintype "passive"))
    )
    (net (code "74") (name "unconnected-(J1-Pad1)") (class "Default")
      (node (ref "J1") (pin "1") (pinfunction "1_1") (pintype "passive"))
    )
    (net (code "75") (name "unconnected-(J1-Pad2)") (class "Default")
      (node (ref "J1") (pin "2") (pinfunction "2_2") (pintype "passive"))
    )
    (net (code "76") (name "unconnected-(J1-Pad13)") (class "Default")
      (node (ref "J1") (pin "13") (pinfunction "13_13") (pintype "passive"))
    )
    (net (code "77") (name "unconnected-(J1-Pad14)") (class "Default")
      (node (ref "J1") (pin "14") (pinfunction "14_14") (pintype "passive"))
    )
    (net (code "78") (name "unconnected-(J1-Pad15)") (class "Default")
      (node (ref "J1") (pin "15") (pinfunction "15_15") (pintype "passive"))
    )
    (net (code "79") (name "unconnected-(J1-Pad16)") (class "Default")
      (node (ref "J1") (pin "16") (pinfunction "16_16") (pintype "passive"))
    )
    (net (code "80") (name "unconnected-(JP1-Pad13)") (class "Default")
      (node (ref "JP1") (pin "13") (pinfunction "13_13") (pintype "passive"))
    )
    (net (code "81") (name "unconnected-(JP2-Pad13)") (class "Default")
      (node (ref "JP2") (pin "13") (pinfunction "13_13") (pintype "passive"))
    )
    (net (code "82") (name "unconnected-(S1-O-Pad1)") (class "Default")
      (node (ref "S1") (pin "1") (pinfunction "O_1") (pintype "passive"))
    )
    (net (code "83") (name "unconnected-(S2-O-Pad1)") (class "Default")
      (node (ref "S2") (pin "1") (pinfunction "O_1") (pintype "passive"))
    )
    (net (code "84") (name "unconnected-(S3-O-Pad1)") (class "Default")
      (node (ref "S3") (pin "1") (pinfunction "O_1") (pintype "passive"))
    )
    (net (code "85") (name "unconnected-(S4-O-Pad1)") (class "Default")
      (node (ref "S4") (pin "1") (pinfunction "O_1") (pintype "passive"))
    )
    (net (code "86") (name "unconnected-(S5-O-Pad1)") (class "Default")
      (node (ref "S5") (pin "1") (pinfunction "O_1") (pintype "passive"))
    )
    (net (code "87") (name "unconnected-(S6-O-Pad1)") (class "Default")
      (node (ref "S6") (pin "1") (pinfunction "O_1") (pintype "passive"))
    )
    (net (code "88") (name "unconnected-(S7-O-Pad1)") (class "Default")
      (node (ref "S7") (pin "1") (pinfunction "O_1") (pintype "passive"))
    )
    (net (code "89") (name "unconnected-(S8-O-Pad1)") (class "Default")
      (node (ref "S8") (pin "1") (pinfunction "O_1") (pintype "passive"))
    )
    (net (code "90") (name "unconnected-(S9-O-Pad1)") (class "Default")
      (node (ref "S9") (pin "1") (pinfunction "O_1") (pintype "passive"))
    )
    (net (code "91") (name "unconnected-(S10-O-Pad1)") (class "Default")
      (node (ref "S10") (pin "1") (pinfunction "O_1") (pintype "passive"))
    )
    (net (code "92") (name "unconnected-(S11-O-Pad1)") (class "Default")
      (node (ref "S11") (pin "1") (pinfunction "O_1") (pintype "passive"))
    )
    (net (code "93") (name "unconnected-(S12-O-Pad1)") (class "Default")
      (node (ref "S12") (pin "1") (pinfunction "O_1") (pintype "passive"))
    )
    (net (code "94") (name "unconnected-(S13-O-Pad1)") (class "Default")
      (node (ref "S13") (pin "1") (pinfunction "O_1") (pintype "passive"))
    )
    (net (code "95") (name "unconnected-(S14-O-Pad1)") (class "Default")
      (node (ref "S14") (pin "1") (pinfunction "O_1") (pintype "passive"))
    )
    (net (code "96") (name "unconnected-(S15-O-Pad1)") (class "Default")
      (node (ref "S15") (pin "1") (pinfunction "O_1") (pintype "passive"))
    )
    (net (code "97") (name "unconnected-(S16-O-Pad1)") (class "Default")
      (node (ref "S16") (pin "1") (pinfunction "O_1") (pintype "passive"))
    )
    (net (code "98") (name "unconnected-(S17-O-Pad1)") (class "Default")
      (node (ref "S17") (pin "1") (pinfunction "O_1") (pintype "passive"))
    )
    (net (code "99") (name "unconnected-(S18-O-Pad1)") (class "Default")
      (node (ref "S18") (pin "1") (pinfunction "O_1") (pintype "passive"))
    )
    (net (code "100") (name "unconnected-(S19-O-Pad1)") (class "Default")
      (node (ref "S19") (pin "1") (pinfunction "O_1") (pintype "passive"))
    )
    (net (code "101") (name "unconnected-(U$1-2-PadP$2)") (class "Default")
      (node (ref "U$1") (pin "P$2") (pinfunction "2_P$2") (pintype "bidirectional"))
    )
    (net (code "102") (name "unconnected-(U$2-2-PadP$2)") (class "Default")
      (node (ref "U$2") (pin "P$2") (pinfunction "2_P$2") (pintype "bidirectional"))
    )
    (net (code "103") (name "unconnected-(U$3-2-PadP$2)") (class "Default")
      (node (ref "U$3") (pin "P$2") (pinfunction "2_P$2") (pintype "bidirectional"))
    )
    (net (code "104") (name "unconnected-(U$4-2-PadP$2)") (class "Default")
      (node (ref "U$4") (pin "P$2") (pinfunction "2_P$2") (pintype "bidirectional"))
    )
    (net (code "105") (name "unconnected-(U$5-2-PadP$2)") (class "Default")
      (node (ref "U$5") (pin "P$2") (pinfunction "2_P$2") (pintype "bidirectional"))
    )
    (net (code "106") (name "unconnected-(U$6-2-PadP$2)") (class "Default")
      (node (ref "U$6") (pin "P$2") (pinfunction "2_P$2") (pintype "bidirectional"))
    )
    (net (code "107") (name "unconnected-(U$7-2-PadP$2)") (class "Default")
      (node (ref "U$7") (pin "P$2") (pinfunction "2_P$2") (pintype "bidirectional"))
    )
    (net (code "108") (name "unconnected-(U$8-2-PadP$2)") (class "Default")
      (node (ref "U$8") (pin "P$2") (pinfunction "2_P$2") (pintype "bidirectional"))
    )
    (net (code "109") (name "unconnected-(U$9-2-PadP$2)") (class "Default")
      (node (ref "U$9") (pin "P$2") (pinfunction "2_P$2") (pintype "bidirectional"))
    )
  )
)
